# shieldAtmegaArianna_00.net
KiCad netlist of a schematic drawn in EAGLE
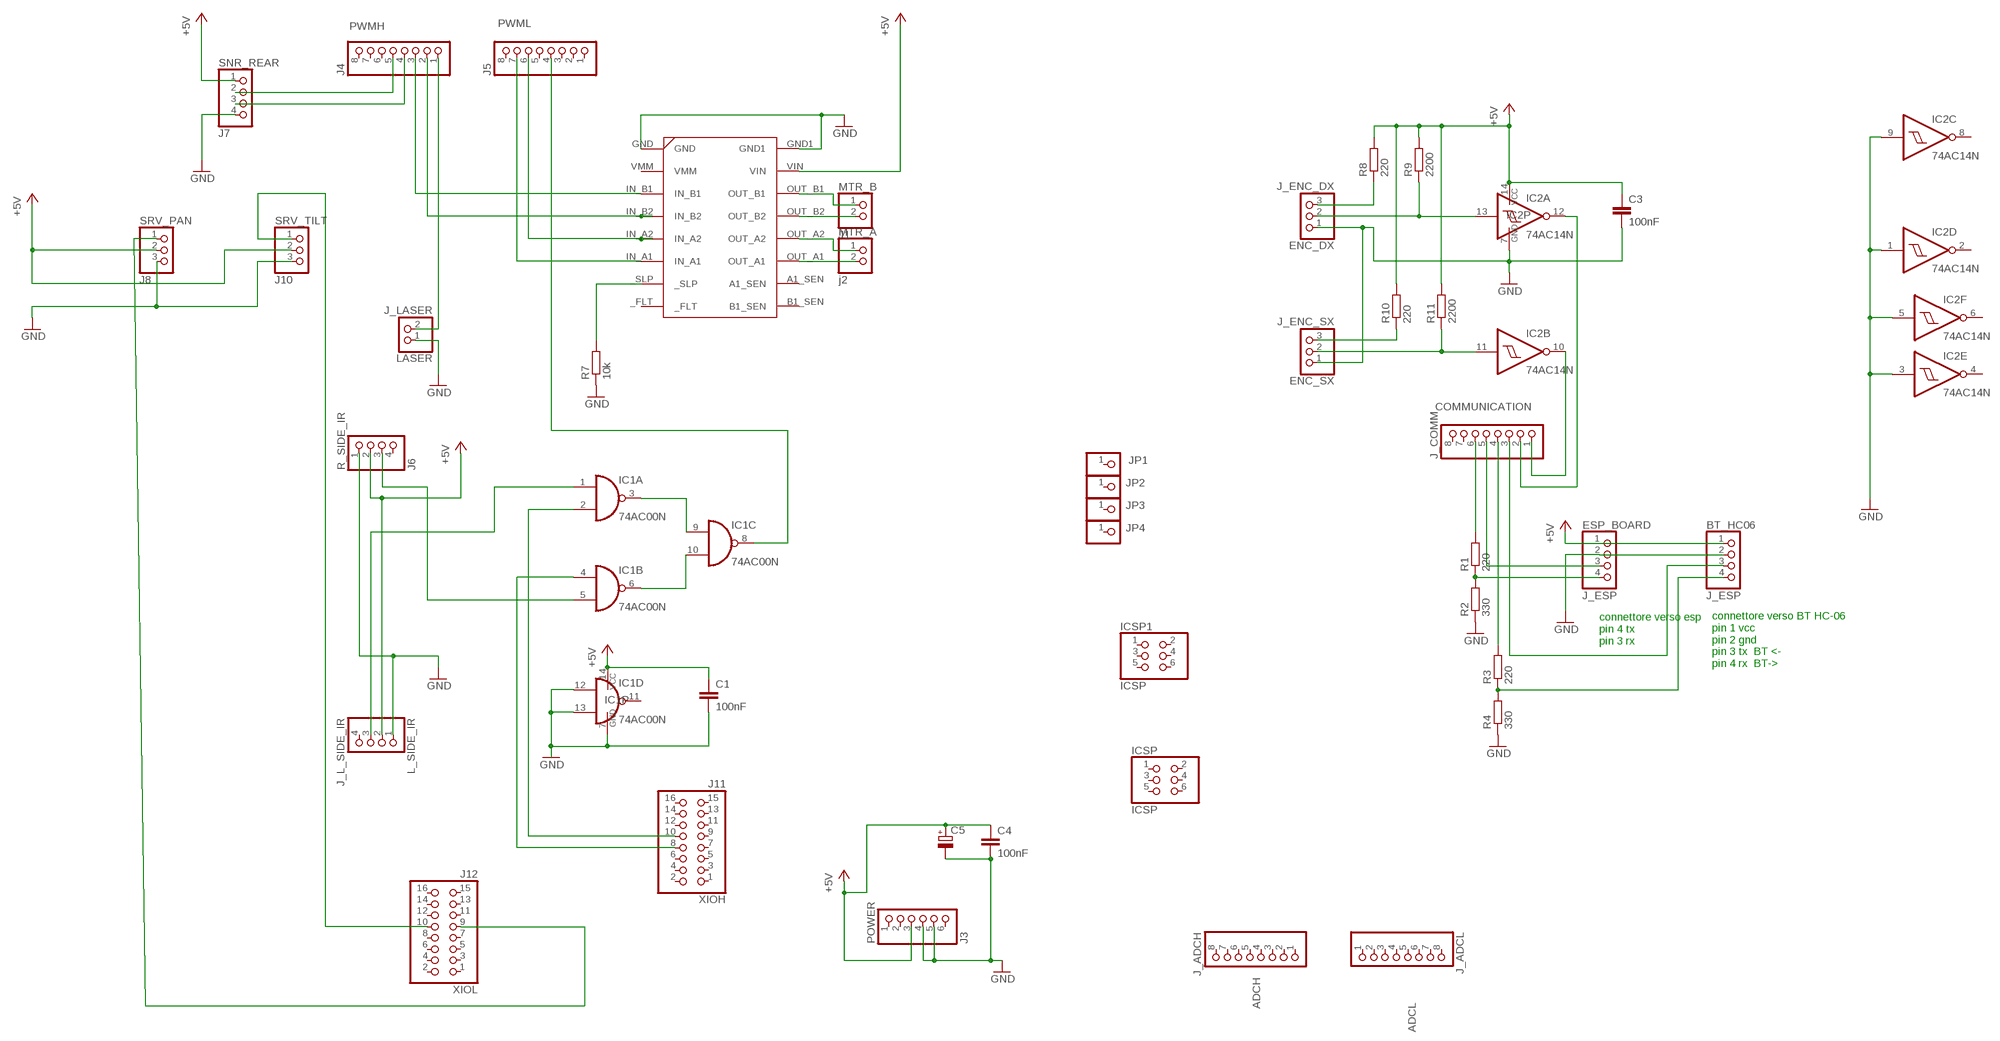
[diagram p0: schematic, sheet 1]

(export (version "E")
  (design (tool "Eeschema 10.0.6"))
  (components
    (comp (ref "ADCH")
      (value "J_ADCH")
      (footprint "eagle-import:1X08")
      (libsource (lib "eagle-import") (part "PINHD-1X8"))
    )
    (comp (ref "ADCL")
      (value "J_ADCL")
      (footprint "eagle-import:1X08")
      (libsource (lib "eagle-import") (part "PINHD-1X8"))
    )
    (comp (ref "BT_HC06")
      (value "J_ESP")
      (footprint "eagle-import:1X04")
      (libsource (lib "eagle-import") (part "PINHD-1X4"))
    )
    (comp (ref "C1")
      (value "100nF")
      (footprint "eagle-import:C050-025X075")
      (libsource (lib "eagle-import") (part "C-EU050-025X075"))
    )
    (comp (ref "C3")
      (value "100nF")
      (footprint "eagle-import:C050-025X075")
      (libsource (lib "eagle-import") (part "C-EU050-025X075"))
    )
    (comp (ref "C4")
      (value "100nF")
      (footprint "eagle-import:C050-025X075")
      (libsource (lib "eagle-import") (part "C-EU050-025X075"))
    )
    (comp (ref "C5")
      (value "CPOL-EUE5-8.5")
      (footprint "eagle-import:E5-8,5")
      (libsource (lib "eagle-import") (part "CPOL-EUE5-8.5"))
    )
    (comp (ref "COMMUNICATION")
      (value "J_COMM")
      (footprint "eagle-import:1X08")
      (libsource (lib "eagle-import") (part "PINHD-1X8"))
    )
    (comp (ref "ENC_DX")
      (value "J_ENC_DX")
      (footprint "eagle-import:1X03")
      (libsource (lib "eagle-import") (part "PINHD-1X3"))
    )
    (comp (ref "ENC_SX")
      (value "J_ENC_SX")
      (footprint "eagle-import:1X03")
      (libsource (lib "eagle-import") (part "PINHD-1X3"))
    )
    (comp (ref "ESP_BOARD")
      (value "J_ESP")
      (footprint "eagle-import:1X04")
      (libsource (lib "eagle-import") (part "PINHD-1X4"))
    )
    (comp (ref "IC1")
      (value "74AC00N")
      (footprint "eagle-import:DIL14")
      (libsource (lib "eagle-import") (part "7400NAC"))
    )
    (comp (ref "IC2")
      (value "74AC14N")
      (footprint "eagle-import:DIL14")
      (libsource (lib "eagle-import") (part "7414NAC"))
    )
    (comp (ref "ICSP")
      (value "ICSP")
      (footprint "eagle-import:2X03")
      (libsource (lib "eagle-import") (part "PINHD-2X3"))
    )
    (comp (ref "ICSP1")
      (value "ICSP")
      (footprint "eagle-import:2X03")
      (libsource (lib "eagle-import") (part "PINHD-2X3"))
    )
    (comp (ref "JP1")
      (value "PINHD-1X1")
      (footprint "eagle-import:1X01")
      (libsource (lib "eagle-import") (part "PINHD-1X1"))
    )
    (comp (ref "JP2")
      (value "PINHD-1X1")
      (footprint "eagle-import:1X01")
      (libsource (lib "eagle-import") (part "PINHD-1X1"))
    )
    (comp (ref "JP3")
      (value "PINHD-1X1")
      (footprint "eagle-import:1X01")
      (libsource (lib "eagle-import") (part "PINHD-1X1"))
    )
    (comp (ref "JP4")
      (value "PINHD-1X1")
      (footprint "eagle-import:1X01")
      (libsource (lib "eagle-import") (part "PINHD-1X1"))
    )
    (comp (ref "LASER")
      (value "J_LASER")
      (footprint "eagle-import:1X02")
      (libsource (lib "eagle-import") (part "PINHD-1X2"))
    )
    (comp (ref "L_SIDE_IR")
      (value "J_L_SIDE_IR")
      (footprint "eagle-import:1X04")
      (libsource (lib "eagle-import") (part "PINHD-1X4"))
    )
    (comp (ref "MTR_A")
      (value "j2")
      (footprint "eagle-import:1X02")
      (libsource (lib "eagle-import") (part "PINHD-1X2"))
    )
    (comp (ref "MTR_B")
      (value "J1")
      (footprint "eagle-import:1X02")
      (libsource (lib "eagle-import") (part "PINHD-1X2"))
    )
    (comp (ref "POWER")
      (value "J3")
      (footprint "eagle-import:1X06")
      (libsource (lib "eagle-import") (part "PINHD-1X6"))
    )
    (comp (ref "PWMH")
      (value "J4")
      (footprint "eagle-import:1X08")
      (libsource (lib "eagle-import") (part "PINHD-1X8"))
    )
    (comp (ref "PWML")
      (value "J5")
      (footprint "eagle-import:1X08")
      (libsource (lib "eagle-import") (part "PINHD-1X8"))
    )
    (comp (ref "R1")
      (value "220")
      (footprint "eagle-import:0207_10")
      (libsource (lib "eagle-import") (part "R-EU_0207/10"))
    )
    (comp (ref "R2")
      (value "330")
      (footprint "eagle-import:0207_10")
      (libsource (lib "eagle-import") (part "R-EU_0207/10"))
    )
    (comp (ref "R3")
      (value "220")
      (footprint "eagle-import:0207_10")
      (libsource (lib "eagle-import") (part "R-EU_0207/10"))
    )
    (comp (ref "R4")
      (value "330")
      (footprint "eagle-import:0207_10")
      (libsource (lib "eagle-import") (part "R-EU_0207/10"))
    )
    (comp (ref "R7")
      (value "10k")
      (footprint "eagle-import:0207_10")
      (libsource (lib "eagle-import") (part "R-EU_0207/10"))
    )
    (comp (ref "R8")
      (value "220")
      (footprint "eagle-import:0207_10")
      (libsource (lib "eagle-import") (part "R-EU_0207/10"))
    )
    (comp (ref "R9")
      (value "2200")
      (footprint "eagle-import:0207_10")
      (libsource (lib "eagle-import") (part "R-EU_0207/10"))
    )
    (comp (ref "R10")
      (value "220")
      (footprint "eagle-import:0207_10")
      (libsource (lib "eagle-import") (part "R-EU_0207/10"))
    )
    (comp (ref "R11")
      (value "2200")
      (footprint "eagle-import:0207_10")
      (libsource (lib "eagle-import") (part "R-EU_0207/10"))
    )
    (comp (ref "R_SIDE_IR")
      (value "J6")
      (footprint "eagle-import:1X04")
      (libsource (lib "eagle-import") (part "PINHD-1X4"))
    )
    (comp (ref "SNR_REAR")
      (value "J7")
      (footprint "eagle-import:1X04")
      (libsource (lib "eagle-import") (part "PINHD-1X4"))
    )
    (comp (ref "SRV_PAN")
      (value "J8")
      (footprint "eagle-import:1X03")
      (libsource (lib "eagle-import") (part "PINHD-1X3"))
    )
    (comp (ref "SRV_TILT")
      (value "J10")
      (footprint "eagle-import:1X03")
      (libsource (lib "eagle-import") (part "PINHD-1X3"))
    )
    (comp (ref "U$1")
      (value "DRV8803")
      (footprint "eagle-import:8X5CARRIER")
      (libsource (lib "eagle-import") (part "DRV8803"))
    )
    (comp (ref "XIOH")
      (value "J11")
      (footprint "eagle-import:2X08")
      (libsource (lib "eagle-import") (part "PINHD-2X8"))
    )
    (comp (ref "XIOL")
      (value "J12")
      (footprint "eagle-import:2X08")
      (libsource (lib "eagle-import") (part "PINHD-2X8"))
    )
  )
  (nets
    (net (code "1") (name "+5V") (class "Default")
      (node (ref "BT_HC06") (pin "1") (pinfunction "1_1") (pintype "passive"))
      (node (ref "C1") (pin "1") (pinfunction "1_1") (pintype "passive"))
      (node (ref "C3") (pin "1") (pinfunction "1_1") (pintype "passive"))
      (node (ref "C4") (pin "1") (pinfunction "1_1") (pintype "passive"))
      (node (ref "C5") (pin "+") (pinfunction "+_+") (pintype "passive"))
      (node (ref "ESP_BOARD") (pin "1") (pinfunction "1_1") (pintype "passive"))
      (node (ref "IC1") (pin "14") (pinfunction "VCC_14") (pintype "power_in"))
      (node (ref "IC2") (pin "14") (pinfunction "VCC_14") (pintype "power_in"))
      (node (ref "L_SIDE_IR") (pin "2") (pinfunction "2_2") (pintype "passive"))
      (node (ref "POWER") (pin "3") (pinfunction "3_3") (pintype "passive"))
      (node (ref "R10") (pin "2") (pinfunction "2_2") (pintype "passive"))
      (node (ref "R11") (pin "2") (pinfunction "2_2") (pintype "passive"))
      (node (ref "R8") (pin "2") (pinfunction "2_2") (pintype "passive"))
      (node (ref "R9") (pin "2") (pinfunction "2_2") (pintype "passive"))
      (node (ref "R_SIDE_IR") (pin "2") (pinfunction "2_2") (pintype "passive"))
      (node (ref "SNR_REAR") (pin "1") (pinfunction "1_1") (pintype "passive"))
      (node (ref "SRV_PAN") (pin "2") (pinfunction "2_2") (pintype "passive"))
      (node (ref "SRV_TILT") (pin "2") (pinfunction "2_2") (pintype "passive"))
      (node (ref "U$1") (pin "VIN") (pinfunction "VIN_VIN") (pintype "bidirectional"))
    )
    (net (code "2") (name "GND") (class "Default")
      (node (ref "BT_HC06") (pin "2") (pinfunction "2_2") (pintype "passive"))
      (node (ref "C1") (pin "2") (pinfunction "2_2") (pintype "passive"))
      (node (ref "C3") (pin "2") (pinfunction "2_2") (pintype "passive"))
      (node (ref "C4") (pin "2") (pinfunction "2_2") (pintype "passive"))
      (node (ref "C5") (pin "-") (pinfunction "-_-") (pintype "passive"))
      (node (ref "ENC_DX") (pin "1") (pinfunction "1_1") (pintype "passive"))
      (node (ref "ENC_SX") (pin "1") (pinfunction "1_1") (pintype "passive"))
      (node (ref "ESP_BOARD") (pin "2") (pinfunction "2_2") (pintype "passive"))
      (node (ref "IC1") (pin "12") (pinfunction "I0_12") (pintype "input"))
      (node (ref "IC1") (pin "13") (pinfunction "I1_13") (pintype "input"))
      (node (ref "IC1") (pin "7") (pinfunction "GND_7") (pintype "power_in"))
      (node (ref "IC2") (pin "1") (pinfunction "I_1") (pintype "input"))
      (node (ref "IC2") (pin "3") (pinfunction "I_3") (pintype "input"))
      (node (ref "IC2") (pin "5") (pinfunction "I_5") (pintype "input"))
      (node (ref "IC2") (pin "7") (pinfunction "GND_7") (pintype "power_in"))
      (node (ref "IC2") (pin "9") (pinfunction "I_9") (pintype "input"))
      (node (ref "LASER") (pin "1") (pinfunction "1_1") (pintype "passive"))
      (node (ref "L_SIDE_IR") (pin "1") (pinfunction "1_1") (pintype "passive"))
      (node (ref "POWER") (pin "4") (pinfunction "4_4") (pintype "passive"))
      (node (ref "POWER") (pin "5") (pinfunction "5_5") (pintype "passive"))
      (node (ref "R2") (pin "1") (pinfunction "1_1") (pintype "passive"))
      (node (ref "R4") (pin "1") (pinfunction "1_1") (pintype "passive"))
      (node (ref "R7") (pin "1") (pinfunction "1_1") (pintype "passive"))
      (node (ref "R_SIDE_IR") (pin "1") (pinfunction "1_1") (pintype "passive"))
      (node (ref "SNR_REAR") (pin "4") (pinfunction "4_4") (pintype "passive"))
      (node (ref "SRV_PAN") (pin "3") (pinfunction "3_3") (pintype "passive"))
      (node (ref "SRV_TILT") (pin "3") (pinfunction "3_3") (pintype "passive"))
      (node (ref "U$1") (pin "GND") (pinfunction "GND_GND") (pintype "bidirectional"))
      (node (ref "U$1") (pin "GND1") (pinfunction "GND1_GND1") (pintype "bidirectional"))
    )
    (net (code "3") (name "Net-(BT_HC06-Pad3)") (class "Default")
      (node (ref "BT_HC06") (pin "3") (pinfunction "3_3") (pintype "passive"))
      (node (ref "COMMUNICATION") (pin "3") (pinfunction "3_3") (pintype "passive"))
    )
    (net (code "4") (name "Net-(BT_HC06-Pad4)") (class "Default")
      (node (ref "BT_HC06") (pin "4") (pinfunction "4_4") (pintype "passive"))
      (node (ref "R3") (pin "1") (pinfunction "1_1") (pintype "passive"))
      (node (ref "R4") (pin "2") (pinfunction "2_2") (pintype "passive"))
    )
    (net (code "5") (name "Net-(COMMUNICATION-Pad4)") (class "Default")
      (node (ref "COMMUNICATION") (pin "4") (pinfunction "4_4") (pintype "passive"))
      (node (ref "R3") (pin "2") (pinfunction "2_2") (pintype "passive"))
    )
    (net (code "6") (name "Net-(COMMUNICATION-Pad5)") (class "Default")
      (node (ref "COMMUNICATION") (pin "5") (pinfunction "5_5") (pintype "passive"))
      (node (ref "ESP_BOARD") (pin "3") (pinfunction "3_3") (pintype "passive"))
    )
    (net (code "7") (name "Net-(COMMUNICATION-Pad6)") (class "Default")
      (node (ref "COMMUNICATION") (pin "6") (pinfunction "6_6") (pintype "passive"))
      (node (ref "R1") (pin "2") (pinfunction "2_2") (pintype "passive"))
    )
    (net (code "8") (name "Net-(ENC_DX-Pad3)") (class "Default")
      (node (ref "ENC_DX") (pin "3") (pinfunction "3_3") (pintype "passive"))
      (node (ref "R8") (pin "1") (pinfunction "1_1") (pintype "passive"))
    )
    (net (code "9") (name "Net-(ENC_SX-Pad3)") (class "Default")
      (node (ref "ENC_SX") (pin "3") (pinfunction "3_3") (pintype "passive"))
      (node (ref "R10") (pin "1") (pinfunction "1_1") (pintype "passive"))
    )
    (net (code "10") (name "Net-(ESP_BOARD-Pad4)") (class "Default")
      (node (ref "ESP_BOARD") (pin "4") (pinfunction "4_4") (pintype "passive"))
      (node (ref "R1") (pin "1") (pinfunction "1_1") (pintype "passive"))
      (node (ref "R2") (pin "2") (pinfunction "2_2") (pintype "passive"))
    )
    (net (code "11") (name "Net-(IC1A-I0)") (class "Default")
      (node (ref "IC1") (pin "1") (pinfunction "I0_1") (pintype "input"))
      (node (ref "L_SIDE_IR") (pin "3") (pinfunction "3_3") (pintype "passive"))
    )
    (net (code "12") (name "Net-(IC1A-I1)") (class "Default")
      (node (ref "IC1") (pin "2") (pinfunction "I1_2") (pintype "input"))
      (node (ref "XIOH") (pin "10") (pinfunction "10_10") (pintype "passive"))
    )
    (net (code "13") (name "Net-(IC1A-O)") (class "Default")
      (node (ref "IC1") (pin "3") (pinfunction "O_3") (pintype "output"))
      (node (ref "IC1") (pin "9") (pinfunction "I0_9") (pintype "input"))
    )
    (net (code "14") (name "Net-(IC1B-I0)") (class "Default")
      (node (ref "IC1") (pin "4") (pinfunction "I0_4") (pintype "input"))
      (node (ref "XIOH") (pin "8") (pinfunction "8_8") (pintype "passive"))
    )
    (net (code "15") (name "Net-(IC1B-I1)") (class "Default")
      (node (ref "IC1") (pin "5") (pinfunction "I1_5") (pintype "input"))
      (node (ref "R_SIDE_IR") (pin "3") (pinfunction "3_3") (pintype "passive"))
    )
    (net (code "16") (name "Net-(IC1B-O)") (class "Default")
      (node (ref "IC1") (pin "10") (pinfunction "I1_10") (pintype "input"))
      (node (ref "IC1") (pin "6") (pinfunction "O_6") (pintype "output"))
    )
    (net (code "17") (name "Net-(IC1C-O)") (class "Default")
      (node (ref "IC1") (pin "8") (pinfunction "O_8") (pintype "output"))
      (node (ref "PWML") (pin "4") (pinfunction "4_4") (pintype "passive"))
    )
    (net (code "18") (name "Net-(IC2A-I)") (class "Default")
      (node (ref "ENC_DX") (pin "2") (pinfunction "2_2") (pintype "passive"))
      (node (ref "IC2") (pin "13") (pinfunction "I_13") (pintype "input"))
      (node (ref "R9") (pin "1") (pinfunction "1_1") (pintype "passive"))
    )
    (net (code "19") (name "Net-(IC2A-O)") (class "Default")
      (node (ref "COMMUNICATION") (pin "2") (pinfunction "2_2") (pintype "passive"))
      (node (ref "IC2") (pin "12") (pinfunction "O_12") (pintype "output"))
    )
    (net (code "20") (name "Net-(IC2B-I)") (class "Default")
      (node (ref "ENC_SX") (pin "2") (pinfunction "2_2") (pintype "passive"))
      (node (ref "IC2") (pin "11") (pinfunction "I_11") (pintype "input"))
      (node (ref "R11") (pin "1") (pinfunction "1_1") (pintype "passive"))
    )
    (net (code "21") (name "Net-(IC2B-O)") (class "Default")
      (node (ref "COMMUNICATION") (pin "1") (pinfunction "1_1") (pintype "passive"))
      (node (ref "IC2") (pin "10") (pinfunction "O_10") (pintype "output"))
    )
    (net (code "22") (name "Net-(LASER-Pad2)") (class "Default")
      (node (ref "LASER") (pin "2") (pinfunction "2_2") (pintype "passive"))
      (node (ref "PWMH") (pin "1") (pinfunction "1_1") (pintype "passive"))
    )
    (net (code "23") (name "Net-(MTR_A-Pad1)") (class "Default")
      (node (ref "MTR_A") (pin "1") (pinfunction "1_1") (pintype "passive"))
      (node (ref "U$1") (pin "OUT_A2") (pinfunction "OUT_A2_OUT_A2") (pintype "bidirectional"))
    )
    (net (code "24") (name "Net-(MTR_A-Pad2)") (class "Default")
      (node (ref "MTR_A") (pin "2") (pinfunction "2_2") (pintype "passive"))
      (node (ref "U$1") (pin "OUT_A1") (pinfunction "OUT_A1_OUT_A1") (pintype "bidirectional"))
    )
    (net (code "25") (name "Net-(MTR_B-Pad1)") (class "Default")
      (node (ref "MTR_B") (pin "1") (pinfunction "1_1") (pintype "passive"))
      (node (ref "U$1") (pin "OUT_B1") (pinfunction "OUT_B1_OUT_B1") (pintype "bidirectional"))
    )
    (net (code "26") (name "Net-(MTR_B-Pad2)") (class "Default")
      (node (ref "MTR_B") (pin "2") (pinfunction "2_2") (pintype "passive"))
      (node (ref "U$1") (pin "OUT_B2") (pinfunction "OUT_B2_OUT_B2") (pintype "bidirectional"))
    )
    (net (code "27") (name "Net-(PWMH-Pad2)") (class "Default")
      (node (ref "PWMH") (pin "2") (pinfunction "2_2") (pintype "passive"))
      (node (ref "U$1") (pin "IN_B2") (pinfunction "IN_B2_IN_B2") (pintype "bidirectional"))
    )
    (net (code "28") (name "Net-(PWMH-Pad3)") (class "Default")
      (node (ref "PWMH") (pin "3") (pinfunction "3_3") (pintype "passive"))
      (node (ref "U$1") (pin "IN_B1") (pinfunction "IN_B1_IN_B1") (pintype "bidirectional"))
    )
    (net (code "29") (name "Net-(PWMH-Pad4)") (class "Default")
      (node (ref "PWMH") (pin "4") (pinfunction "4_4") (pintype "passive"))
      (node (ref "SNR_REAR") (pin "3") (pinfunction "3_3") (pintype "passive"))
    )
    (net (code "30") (name "Net-(PWMH-Pad5)") (class "Default")
      (node (ref "PWMH") (pin "5") (pinfunction "5_5") (pintype "passive"))
      (node (ref "SNR_REAR") (pin "2") (pinfunction "2_2") (pintype "passive"))
    )
    (net (code "31") (name "Net-(PWML-Pad6)") (class "Default")
      (node (ref "PWML") (pin "6") (pinfunction "6_6") (pintype "passive"))
      (node (ref "U$1") (pin "IN_A2") (pinfunction "IN_A2_IN_A2") (pintype "bidirectional"))
    )
    (net (code "32") (name "Net-(PWML-Pad7)") (class "Default")
      (node (ref "PWML") (pin "7") (pinfunction "7_7") (pintype "passive"))
      (node (ref "U$1") (pin "IN_A1") (pinfunction "IN_A1_IN_A1") (pintype "bidirectional"))
    )
    (net (code "33") (name "Net-(R7-Pad2)") (class "Default")
      (node (ref "R7") (pin "2") (pinfunction "2_2") (pintype "passive"))
      (node (ref "U$1") (pin "_SLP") (pinfunction "_SLP__SLP") (pintype "bidirectional"))
    )
    (net (code "34") (name "Net-(SRV_PAN-Pad1)") (class "Default")
      (node (ref "SRV_PAN") (pin "1") (pinfunction "1_1") (pintype "passive"))
      (node (ref "XIOL") (pin "9") (pinfunction "9_9") (pintype "passive"))
    )
    (net (code "35") (name "Net-(SRV_TILT-Pad1)") (class "Default")
      (node (ref "SRV_TILT") (pin "1") (pinfunction "1_1") (pintype "passive"))
      (node (ref "XIOL") (pin "10") (pinfunction "10_10") (pintype "passive"))
    )
    (net (code "36") (name "unconnected-(ADCH-Pad1)") (class "Default")
      (node (ref "ADCH") (pin "1") (pinfunction "1_1") (pintype "passive"))
    )
    (net (code "37") (name "unconnected-(ADCH-Pad2)") (class "Default")
      (node (ref "ADCH") (pin "2") (pinfunction "2_2") (pintype "passive"))
    )
    (net (code "38") (name "unconnected-(ADCH-Pad3)") (class "Default")
      (node (ref "ADCH") (pin "3") (pinfunction "3_3") (pintype "passive"))
    )
    (net (code "39") (name "unconnected-(ADCH-Pad4)") (class "Default")
      (node (ref "ADCH") (pin "4") (pinfunction "4_4") (pintype "passive"))
    )
    (net (code "40") (name "unconnected-(ADCH-Pad5)") (class "Default")
      (node (ref "ADCH") (pin "5") (pinfunction "5_5") (pintype "passive"))
    )
    (net (code "41") (name "unconnected-(ADCH-Pad6)") (class "Default")
      (node (ref "ADCH") (pin "6") (pinfunction "6_6") (pintype "passive"))
    )
    (net (code "42") (name "unconnected-(ADCH-Pad7)") (class "Default")
      (node (ref "ADCH") (pin "7") (pinfunction "7_7") (pintype "passive"))
    )
    (net (code "43") (name "unconnected-(ADCH-Pad8)") (class "Default")
      (node (ref "ADCH") (pin "8") (pinfunction "8_8") (pintype "passive"))
    )
    (net (code "44") (name "unconnected-(ADCL-Pad1)") (class "Default")
      (node (ref "ADCL") (pin "1") (pinfunction "1_1") (pintype "passive"))
    )
    (net (code "45") (name "unconnected-(ADCL-Pad2)") (class "Default")
      (node (ref "ADCL") (pin "2") (pinfunction "2_2") (pintype "passive"))
    )
    (net (code "46") (name "unconnected-(ADCL-Pad3)") (class "Default")
      (node (ref "ADCL") (pin "3") (pinfunction "3_3") (pintype "passive"))
    )
    (net (code "47") (name "unconnected-(ADCL-Pad4)") (class "Default")
      (node (ref "ADCL") (pin "4") (pinfunction "4_4") (pintype "passive"))
    )
    (net (code "48") (name "unconnected-(ADCL-Pad5)") (class "Default")
      (node (ref "ADCL") (pin "5") (pinfunction "5_5") (pintype "passive"))
    )
    (net (code "49") (name "unconnected-(ADCL-Pad6)") (class "Default")
      (node (ref "ADCL") (pin "6") (pinfunction "6_6") (pintype "passive"))
    )
    (net (code "50") (name "unconnected-(ADCL-Pad7)") (class "Default")
      (node (ref "ADCL") (pin "7") (pinfunction "7_7") (pintype "passive"))
    )
    (net (code "51") (name "unconnected-(ADCL-Pad8)") (class "Default")
      (node (ref "ADCL") (pin "8") (pinfunction "8_8") (pintype "passive"))
    )
    (net (code "52") (name "unconnected-(COMMUNICATION-Pad7)") (class "Default")
      (node (ref "COMMUNICATION") (pin "7") (pinfunction "7_7") (pintype "passive"))
    )
    (net (code "53") (name "unconnected-(COMMUNICATION-Pad8)") (class "Default")
      (node (ref "COMMUNICATION") (pin "8") (pinfunction "8_8") (pintype "passive"))
    )
    (net (code "54") (name "unconnected-(IC1D-O-Pad11)") (class "Default")
      (node (ref "IC1") (pin "11") (pinfunction "O_11") (pintype "output"))
    )
    (net (code "55") (name "unconnected-(IC2C-O-Pad8)") (class "Default")
      (node (ref "IC2") (pin "8") (pinfunction "O_8") (pintype "output"))
    )
    (net (code "56") (name "unconnected-(IC2D-O-Pad2)") (class "Default")
      (node (ref "IC2") (pin "2") (pinfunction "O_2") (pintype "output"))
    )
    (net (code "57") (name "unconnected-(IC2E-O-Pad4)") (class "Default")
      (node (ref "IC2") (pin "4") (pinfunction "O_4") (pintype "output"))
    )
    (net (code "58") (name "unconnected-(IC2F-O-Pad6)") (class "Default")
      (node (ref "IC2") (pin "6") (pinfunction "O_6") (pintype "output"))
    )
    (net (code "59") (name "unconnected-(ICSP-Pad1)") (class "Default")
      (node (ref "ICSP") (pin "1") (pinfunction "1_1") (pintype "passive"))
    )
    (net (code "60") (name "unconnected-(ICSP-Pad2)") (class "Default")
      (node (ref "ICSP") (pin "2") (pinfunction "2_2") (pintype "passive"))
    )
    (net (code "61") (name "unconnected-(ICSP-Pad3)") (class "Default")
      (node (ref "ICSP") (pin "3") (pinfunction "3_3") (pintype "passive"))
    )
    (net (code "62") (name "unconnected-(ICSP-Pad4)") (class "Default")
      (node (ref "ICSP") (pin "4") (pinfunction "4_4") (pintype "passive"))
    )
    (net (code "63") (name "unconnected-(ICSP-Pad5)") (class "Default")
      (node (ref "ICSP") (pin "5") (pinfunction "5_5") (pintype "passive"))
    )
    (net (code "64") (name "unconnected-(ICSP-Pad6)") (class "Default")
      (node (ref "ICSP") (pin "6") (pinfunction "6_6") (pintype "passive"))
    )
    (net (code "65") (name "unconnected-(ICSP1-Pad1)") (class "Default")
      (node (ref "ICSP1") (pin "1") (pinfunction "1_1") (pintype "passive"))
    )
    (net (code "66") (name "unconnected-(ICSP1-Pad2)") (class "Default")
      (node (ref "ICSP1") (pin "2") (pinfunction "2_2") (pintype "passive"))
    )
    (net (code "67") (name "unconnected-(ICSP1-Pad3)") (class "Default")
      (node (ref "ICSP1") (pin "3") (pinfunction "3_3") (pintype "passive"))
    )
    (net (code "68") (name "unconnected-(ICSP1-Pad4)") (class "Default")
      (node (ref "ICSP1") (pin "4") (pinfunction "4_4") (pintype "passive"))
    )
    (net (code "69") (name "unconnected-(ICSP1-Pad5)") (class "Default")
      (node (ref "ICSP1") (pin "5") (pinfunction "5_5") (pintype "passive"))
    )
    (net (code "70") (name "unconnected-(ICSP1-Pad6)") (class "Default")
      (node (ref "ICSP1") (pin "6") (pinfunction "6_6") (pintype "passive"))
    )
    (net (code "71") (name "unconnected-(JP1-Pad1)") (class "Default")
      (node (ref "JP1") (pin "1") (pinfunction "1_1") (pintype "passive"))
    )
    (net (code "72") (name "unconnected-(JP2-Pad1)") (class "Default")
      (node (ref "JP2") (pin "1") (pinfunction "1_1") (pintype "passive"))
    )
    (net (code "73") (name "unconnected-(JP3-Pad1)") (class "Default")
      (node (ref "JP3") (pin "1") (pinfunction "1_1") (pintype "passive"))
    )
    (net (code "74") (name "unconnected-(JP4-Pad1)") (class "Default")
      (node (ref "JP4") (pin "1") (pinfunction "1_1") (pintype "passive"))
    )
    (net (code "75") (name "unconnected-(L_SIDE_IR-Pad4)") (class "Default")
      (node (ref "L_SIDE_IR") (pin "4") (pinfunction "4_4") (pintype "passive"))
    )
    (net (code "76") (name "unconnected-(POWER-Pad1)") (class "Default")
      (node (ref "POWER") (pin "1") (pinfunction "1_1") (pintype "passive"))
    )
    (net (code "77") (name "unconnected-(POWER-Pad2)") (class "Default")
      (node (ref "POWER") (pin "2") (pinfunction "2_2") (pintype "passive"))
    )
    (net (code "78") (name "unconnected-(POWER-Pad6)") (class "Default")
      (node (ref "POWER") (pin "6") (pinfunction "6_6") (pintype "passive"))
    )
    (net (code "79") (name "unconnected-(PWMH-Pad6)") (class "Default")
      (node (ref "PWMH") (pin "6") (pinfunction "6_6") (pintype "passive"))
    )
    (net (code "80") (name "unconnected-(PWMH-Pad7)") (class "Default")
      (node (ref "PWMH") (pin "7") (pinfunction "7_7") (pintype "passive"))
    )
    (net (code "81") (name "unconnected-(PWMH-Pad8)") (class "Default")
      (node (ref "PWMH") (pin "8") (pinfunction "8_8") (pintype "passive"))
    )
    (net (code "82") (name "unconnected-(PWML-Pad1)") (class "Default")
      (node (ref "PWML") (pin "1") (pinfunction "1_1") (pintype "passive"))
    )
    (net (code "83") (name "unconnected-(PWML-Pad2)") (class "Default")
      (node (ref "PWML") (pin "2") (pinfunction "2_2") (pintype "passive"))
    )
    (net (code "84") (name "unconnected-(PWML-Pad3)") (class "Default")
      (node (ref "PWML") (pin "3") (pinfunction "3_3") (pintype "passive"))
    )
    (net (code "85") (name "unconnected-(PWML-Pad5)") (class "Default")
      (node (ref "PWML") (pin "5") (pinfunction "5_5") (pintype "passive"))
    )
    (net (code "86") (name "unconnected-(PWML-Pad8)") (class "Default")
      (node (ref "PWML") (pin "8") (pinfunction "8_8") (pintype "passive"))
    )
    (net (code "87") (name "unconnected-(R_SIDE_IR-Pad4)") (class "Default")
      (node (ref "R_SIDE_IR") (pin "4") (pinfunction "4_4") (pintype "passive"))
    )
    (net (code "88") (name "unconnected-(U$1-PadA1_SEN)") (class "Default")
      (node (ref "U$1") (pin "A1_SEN") (pinfunction "A1_SEN_A1_SEN") (pintype "bidirectional"))
    )
    (net (code "89") (name "unconnected-(U$1-PadB1_SEN)") (class "Default")
      (node (ref "U$1") (pin "B1_SEN") (pinfunction "B1_SEN_B1_SEN") (pintype "bidirectional"))
    )
    (net (code "90") (name "unconnected-(U$1-PadVMM)") (class "Default")
      (node (ref "U$1") (pin "VMM") (pinfunction "VMM_VMM") (pintype "bidirectional"))
    )
    (net (code "91") (name "unconnected-(U$1-Pad_FLT)") (class "Default")
      (node (ref "U$1") (pin "_FLT") (pinfunction "_FLT__FLT") (pintype "bidirectional"))
    )
    (net (code "92") (name "unconnected-(XIOH-Pad1)") (class "Default")
      (node (ref "XIOH") (pin "1") (pinfunction "1_1") (pintype "passive"))
    )
    (net (code "93") (name "unconnected-(XIOH-Pad2)") (class "Default")
      (node (ref "XIOH") (pin "2") (pinfunction "2_2") (pintype "passive"))
    )
    (net (code "94") (name "unconnected-(XIOH-Pad3)") (class "Default")
      (node (ref "XIOH") (pin "3") (pinfunction "3_3") (pintype "passive"))
    )
    (net (code "95") (name "unconnected-(XIOH-Pad4)") (class "Default")
      (node (ref "XIOH") (pin "4") (pinfunction "4_4") (pintype "passive"))
    )
    (net (code "96") (name "unconnected-(XIOH-Pad5)") (class "Default")
      (node (ref "XIOH") (pin "5") (pinfunction "5_5") (pintype "passive"))
    )
    (net (code "97") (name "unconnected-(XIOH-Pad6)") (class "Default")
      (node (ref "XIOH") (pin "6") (pinfunction "6_6") (pintype "passive"))
    )
    (net (code "98") (name "unconnected-(XIOH-Pad7)") (class "Default")
      (node (ref "XIOH") (pin "7") (pinfunction "7_7") (pintype "passive"))
    )
    (net (code "99") (name "unconnected-(XIOH-Pad9)") (class "Default")
      (node (ref "XIOH") (pin "9") (pinfunction "9_9") (pintype "passive"))
    )
    (net (code "100") (name "unconnected-(XIOH-Pad11)") (class "Default")
      (node (ref "XIOH") (pin "11") (pinfunction "11_11") (pintype "passive"))
    )
    (net (code "101") (name "unconnected-(XIOH-Pad12)") (class "Default")
      (node (ref "XIOH") (pin "12") (pinfunction "12_12") (pintype "passive"))
    )
    (net (code "102") (name "unconnected-(XIOH-Pad13)") (class "Default")
      (node (ref "XIOH") (pin "13") (pinfunction "13_13") (pintype "passive"))
    )
    (net (code "103") (name "unconnected-(XIOH-Pad14)") (class "Default")
      (node (ref "XIOH") (pin "14") (pinfunction "14_14") (pintype "passive"))
    )
    (net (code "104") (name "unconnected-(XIOH-Pad15)") (class "Default")
      (node (ref "XIOH") (pin "15") (pinfunction "15_15") (pintype "passive"))
    )
    (net (code "105") (name "unconnected-(XIOH-Pad16)") (class "Default")
      (node (ref "XIOH") (pin "16") (pinfunction "16_16") (pintype "passive"))
    )
    (net (code "106") (name "unconnected-(XIOL-Pad1)") (class "Default")
      (node (ref "XIOL") (pin "1") (pinfunction "1_1") (pintype "passive"))
    )
    (net (code "107") (name "unconnected-(XIOL-Pad2)") (class "Default")
      (node (ref "XIOL") (pin "2") (pinfunction "2_2") (pintype "passive"))
    )
    (net (code "108") (name "unconnected-(XIOL-Pad3)") (class "Default")
      (node (ref "XIOL") (pin "3") (pinfunction "3_3") (pintype "passive"))
    )
    (net (code "109") (name "unconnected-(XIOL-Pad4)") (class "Default")
      (node (ref "XIOL") (pin "4") (pinfunction "4_4") (pintype "passive"))
    )
    (net (code "110") (name "unconnected-(XIOL-Pad5)") (class "Default")
      (node (ref "XIOL") (pin "5") (pinfunction "5_5") (pintype "passive"))
    )
    (net (code "111") (name "unconnected-(XIOL-Pad6)") (class "Default")
      (node (ref "XIOL") (pin "6") (pinfunction "6_6") (pintype "passive"))
    )
    (net (code "112") (name "unconnected-(XIOL-Pad7)") (class "Default")
      (node (ref "XIOL") (pin "7") (pinfunction "7_7") (pintype "passive"))
    )
    (net (code "113") (name "unconnected-(XIOL-Pad8)") (class "Default")
      (node (ref "XIOL") (pin "8") (pinfunction "8_8") (pintype "passive"))
    )
    (net (code "114") (name "unconnected-(XIOL-Pad11)") (class "Default")
      (node (ref "XIOL") (pin "11") (pinfunction "11_11") (pintype "passive"))
    )
    (net (code "115") (name "unconnected-(XIOL-Pad12)") (class "Default")
      (node (ref "XIOL") (pin "12") (pinfunction "12_12") (pintype "passive"))
    )
    (net (code "116") (name "unconnected-(XIOL-Pad13)") (class "Default")
      (node (ref "XIOL") (pin "13") (pinfunction "13_13") (pintype "passive"))
    )
    (net (code "117") (name "unconnected-(XIOL-Pad14)") (class "Default")
      (node (ref "XIOL") (pin "14") (pinfunction "14_14") (pintype "passive"))
    )
    (net (code "118") (name "unconnected-(XIOL-Pad15)") (class "Default")
      (node (ref "XIOL") (pin "15") (pinfunction "15_15") (pintype "passive"))
    )
    (net (code "119") (name "unconnected-(XIOL-Pad16)") (class "Default")
      (node (ref "XIOL") (pin "16") (pinfunction "16_16") (pintype "passive"))
    )
  )
)
